# Output_Connector.net
KiCad netlist of a schematic drawn in Altium Designer
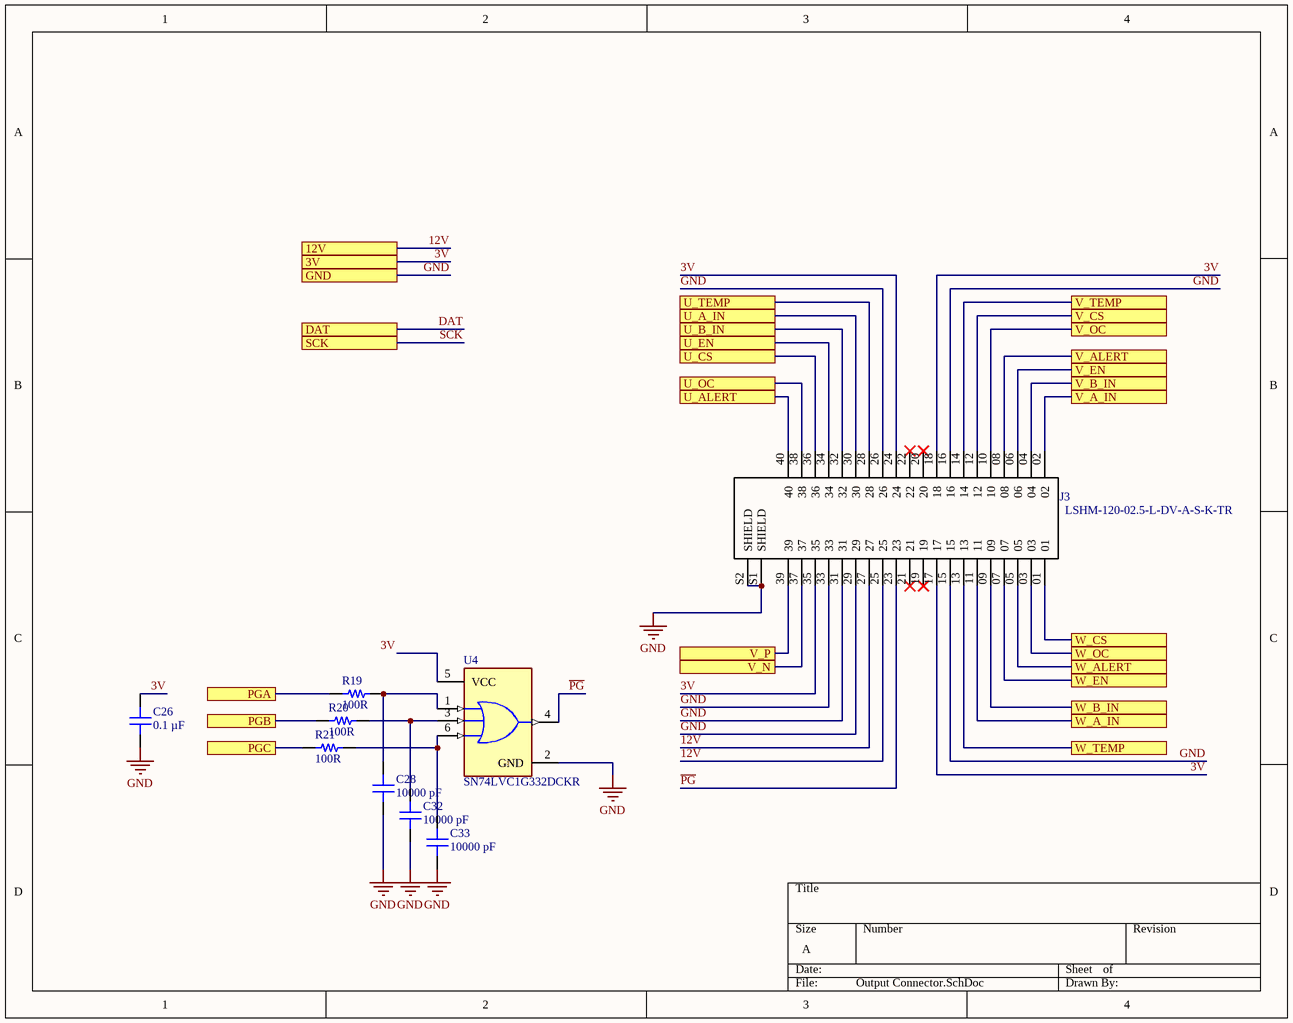
[diagram p0: Output Connector.SchDoc]

(export (version "E")
  (design (tool "Eeschema 10.0.6"))
  (components
    (comp (ref "C26")
      (value "0.1 µF")
      (footprint "CAP 0603_1608")
      (description "CAP CER 0.1UF 50V X7R 0603")
      (fields
        (field (name "PART NUMBER") "C0603C104K5RAC7411")
        (field (name "CAPACITANCE") "0.1 µF")
        (field (name "MANUFACTURER") "KEMET")
      )
      (libsource (lib "Celestial Altium Library - altium_library") (part "Capacitor"))
    )
    (comp (ref "C28")
      (value "10000 pF")
      (footprint "CAP 0402_1005")
      (description "CAP CER 10000PF 16V X7R 0402")
      (fields
        (field (name "PART NUMBER") "C0402C103K4RECAUTO")
        (field (name "CAPACITANCE") "10000 pF")
        (field (name "MANUFACTURER") "KEMET")
      )
      (libsource (lib "Celestial Altium Library - altium_library") (part "Capacitor"))
    )
    (comp (ref "C32")
      (value "10000 pF")
      (footprint "CAP 0402_1005")
      (description "CAP CER 10000PF 16V X7R 0402")
      (fields
        (field (name "PART NUMBER") "C0402C103K4RECAUTO")
        (field (name "CAPACITANCE") "10000 pF")
        (field (name "MANUFACTURER") "KEMET")
      )
      (libsource (lib "Celestial Altium Library - altium_library") (part "Capacitor"))
    )
    (comp (ref "C33")
      (value "10000 pF")
      (footprint "CAP 0402_1005")
      (description "CAP CER 10000PF 16V X7R 0402")
      (fields
        (field (name "PART NUMBER") "C0402C103K4RECAUTO")
        (field (name "CAPACITANCE") "10000 pF")
        (field (name "MANUFACTURER") "KEMET")
      )
      (libsource (lib "Celestial Altium Library - altium_library") (part "Capacitor"))
    )
    (comp (ref "J3")
      (value "LSHM-120-02.5-L-DV-A-S-K-TR")
      (footprint "*SAMTEC_LSHM-120-02.5-L-DV-A-S-K-TR_LSHM-120-02.5-L-DV-A-S-K-TR(Primary)")
      (libsource (lib "Schlib2") (part "LSHM-120-02.5-L-DV-A-S-K-TR"))
    )
    (comp (ref "R19")
      (value "100R")
      (footprint "RES 0402_1005")
      (description "RES 249K OHM 0.1% 1/10W 0402")
      (fields
        (field (name "PART NUMBER") "RP73PF1E249KBTD")
        (field (name "MANUFACTURER") "TE Connectivity Passive Product")
      )
      (libsource (lib "Celestial Altium Library - altium_library") (part "Resistor"))
    )
    (comp (ref "R20")
      (value "100R")
      (footprint "RES 0402_1005")
      (description "RES 249K OHM 0.1% 1/10W 0402")
      (fields
        (field (name "PART NUMBER") "RP73PF1E249KBTD")
        (field (name "MANUFACTURER") "TE Connectivity Passive Product")
      )
      (libsource (lib "Celestial Altium Library - altium_library") (part "Resistor"))
    )
    (comp (ref "R21")
      (value "100R")
      (footprint "RES 0402_1005")
      (description "RES 249K OHM 0.1% 1/10W 0402")
      (fields
        (field (name "PART NUMBER") "RP73PF1E249KBTD")
        (field (name "MANUFACTURER") "TE Connectivity Passive Product")
      )
      (libsource (lib "Celestial Altium Library - altium_library") (part "Resistor"))
    )
    (comp (ref "U4")
      (value "SN74LVC1G332DCKR")
      (footprint "FP-DCK0006A-MFG")
      (description "IC GATE OR 1CH 3-INP SC70-6")
      (fields
        (field (name "MANUFACTURER") "Texas Instruments")
        (field (name "OCTOPART") "https://octopart.com/sn74lvc1g332dckr-texas+instruments-464861")
      )
      (libsource (lib "Altium Content Vault") (part "a1fbee6839145229a27344b52c53a8d"))
    )
  )
  (nets
    (net (code "1") (name "/3V") (class "Default")
      (node (ref "C26") (pin "2") (pinfunction "2_2") (pintype "passive"))
      (node (ref "J3") (pin "17") (pinfunction "17_17") (pintype "passive"))
      (node (ref "J3") (pin "18") (pinfunction "18_18") (pintype "passive"))
      (node (ref "J3") (pin "24") (pinfunction "24_24") (pintype "passive"))
      (node (ref "J3") (pin "35") (pinfunction "35_35") (pintype "passive"))
      (node (ref "U4") (pin "5") (pinfunction "VCC_5") (pintype "power_in"))
    )
    (net (code "2") (name "/12V") (class "Default")
      (node (ref "J3") (pin "25") (pinfunction "25_25") (pintype "passive"))
      (node (ref "J3") (pin "27") (pinfunction "27_27") (pintype "passive"))
    )
    (net (code "4") (name "/PGA") (class "Default")
      (node (ref "R19") (pin "1") (pinfunction "1_1") (pintype "passive"))
    )
    (net (code "5") (name "/PGB") (class "Default")
      (node (ref "R20") (pin "1") (pinfunction "1_1") (pintype "passive"))
    )
    (net (code "6") (name "/PGC") (class "Default")
      (node (ref "R21") (pin "1") (pinfunction "1_1") (pintype "passive"))
    )
    (net (code "8") (name "/U_ALERT") (class "Default")
      (node (ref "J3") (pin "40") (pinfunction "40_40") (pintype "passive"))
    )
    (net (code "9") (name "/U_A_IN") (class "Default")
      (node (ref "J3") (pin "30") (pinfunction "30_30") (pintype "passive"))
    )
    (net (code "10") (name "/U_B_IN") (class "Default")
      (node (ref "J3") (pin "32") (pinfunction "32_32") (pintype "passive"))
    )
    (net (code "11") (name "/U_CS") (class "Default")
      (node (ref "J3") (pin "36") (pinfunction "36_36") (pintype "passive"))
    )
    (net (code "12") (name "/U_EN") (class "Default")
      (node (ref "J3") (pin "34") (pinfunction "34_34") (pintype "passive"))
    )
    (net (code "13") (name "/U_OC") (class "Default")
      (node (ref "J3") (pin "38") (pinfunction "38_38") (pintype "passive"))
    )
    (net (code "14") (name "/U_TEMP") (class "Default")
      (node (ref "J3") (pin "28") (pinfunction "28_28") (pintype "passive"))
    )
    (net (code "15") (name "/V_ALERT") (class "Default")
      (node (ref "J3") (pin "08") (pinfunction "08_08") (pintype "passive"))
    )
    (net (code "16") (name "/V_A_IN") (class "Default")
      (node (ref "J3") (pin "02") (pinfunction "02_02") (pintype "passive"))
    )
    (net (code "17") (name "/V_B_IN") (class "Default")
      (node (ref "J3") (pin "04") (pinfunction "04_04") (pintype "passive"))
    )
    (net (code "18") (name "/V_CS") (class "Default")
      (node (ref "J3") (pin "12") (pinfunction "12_12") (pintype "passive"))
    )
    (net (code "19") (name "/V_EN") (class "Default")
      (node (ref "J3") (pin "06") (pinfunction "06_06") (pintype "passive"))
    )
    (net (code "20") (name "/V_N") (class "Default")
      (node (ref "J3") (pin "37") (pinfunction "37_37") (pintype "passive"))
    )
    (net (code "21") (name "/V_OC") (class "Default")
      (node (ref "J3") (pin "10") (pinfunction "10_10") (pintype "passive"))
    )
    (net (code "22") (name "/V_P") (class "Default")
      (node (ref "J3") (pin "39") (pinfunction "39_39") (pintype "passive"))
    )
    (net (code "23") (name "/V_TEMP") (class "Default")
      (node (ref "J3") (pin "14") (pinfunction "14_14") (pintype "passive"))
    )
    (net (code "24") (name "/W_ALERT") (class "Default")
      (node (ref "J3") (pin "05") (pinfunction "05_05") (pintype "passive"))
    )
    (net (code "25") (name "/W_A_IN") (class "Default")
      (node (ref "J3") (pin "11") (pinfunction "11_11") (pintype "passive"))
    )
    (net (code "26") (name "/W_B_IN") (class "Default")
      (node (ref "J3") (pin "09") (pinfunction "09_09") (pintype "passive"))
    )
    (net (code "27") (name "/W_CS") (class "Default")
      (node (ref "J3") (pin "01") (pinfunction "01_01") (pintype "passive"))
    )
    (net (code "28") (name "/W_EN") (class "Default")
      (node (ref "J3") (pin "07") (pinfunction "07_07") (pintype "passive"))
    )
    (net (code "29") (name "/W_OC") (class "Default")
      (node (ref "J3") (pin "03") (pinfunction "03_03") (pintype "passive"))
    )
    (net (code "30") (name "/W_TEMP") (class "Default")
      (node (ref "J3") (pin "13") (pinfunction "13_13") (pintype "passive"))
    )
    (net (code "31") (name "/~{PG}") (class "Default")
      (node (ref "J3") (pin "23") (pinfunction "23_23") (pintype "passive"))
      (node (ref "U4") (pin "4") (pinfunction "Y_4") (pintype "output"))
    )
    (net (code "32") (name "GND") (class "Default")
      (node (ref "C26") (pin "1") (pinfunction "1_1") (pintype "passive"))
      (node (ref "C28") (pin "1") (pinfunction "1_1") (pintype "passive"))
      (node (ref "C32") (pin "1") (pinfunction "1_1") (pintype "passive"))
      (node (ref "C33") (pin "1") (pinfunction "1_1") (pintype "passive"))
      (node (ref "J3") (pin "15") (pinfunction "15_15") (pintype "passive"))
      (node (ref "J3") (pin "16") (pinfunction "16_16") (pintype "passive"))
      (node (ref "J3") (pin "26") (pinfunction "26_26") (pintype "passive"))
      (node (ref "J3") (pin "29") (pinfunction "29_29") (pintype "passive"))
      (node (ref "J3") (pin "31") (pinfunction "31_31") (pintype "passive"))
      (node (ref "J3") (pin "33") (pinfunction "33_33") (pintype "passive"))
      (node (ref "J3") (pin "S1") (pinfunction "SHIELD_S1") (pintype "passive"))
      (node (ref "J3") (pin "S2") (pinfunction "SHIELD_S2") (pintype "passive"))
      (node (ref "U4") (pin "2") (pinfunction "GND_2") (pintype "power_in"))
    )
    (net (code "33") (name "Net-(U4-A)") (class "Default")
      (node (ref "C28") (pin "2") (pinfunction "2_2") (pintype "passive"))
      (node (ref "R19") (pin "2") (pinfunction "2_2") (pintype "passive"))
      (node (ref "U4") (pin "1") (pinfunction "A_1") (pintype "input"))
    )
    (net (code "34") (name "Net-(U4-B)") (class "Default")
      (node (ref "C32") (pin "2") (pinfunction "2_2") (pintype "passive"))
      (node (ref "R20") (pin "2") (pinfunction "2_2") (pintype "passive"))
      (node (ref "U4") (pin "3") (pinfunction "B_3") (pintype "input"))
    )
    (net (code "35") (name "Net-(U4-C)") (class "Default")
      (node (ref "C33") (pin "2") (pinfunction "2_2") (pintype "passive"))
      (node (ref "R21") (pin "2") (pinfunction "2_2") (pintype "passive"))
      (node (ref "U4") (pin "6") (pinfunction "C_6") (pintype "input"))
    )
    (net (code "36") (name "unconnected-(J3-Pad19)") (class "Default")
      (node (ref "J3") (pin "19") (pinfunction "19_19") (pintype "passive+no_connect"))
    )
    (net (code "37") (name "unconnected-(J3-Pad20)") (class "Default")
      (node (ref "J3") (pin "20") (pinfunction "20_20") (pintype "passive+no_connect"))
    )
    (net (code "38") (name "unconnected-(J3-Pad21)") (class "Default")
      (node (ref "J3") (pin "21") (pinfunction "21_21") (pintype "passive+no_connect"))
    )
    (net (code "39") (name "unconnected-(J3-Pad22)") (class "Default")
      (node (ref "J3") (pin "22") (pinfunction "22_22") (pintype "passive+no_connect"))
    )
  )
)
